# DIV30.net
KiCad netlist of a schematic drawn in Altium Designer
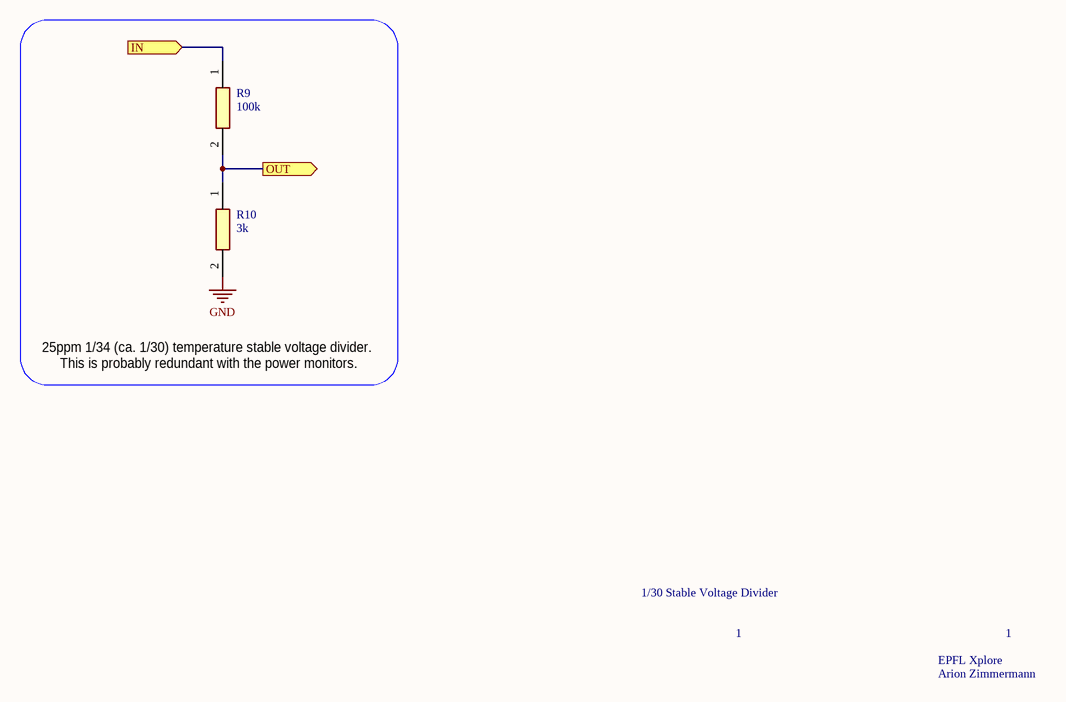
[diagram p0: DIV30.SchDoc]

(export (version "E")
  (design (tool "Eeschema 10.0.6"))
  (components
    (comp (ref "R9")
      (value "100k")
      (footprint "SamacSys:RESC1608X55N")
      (description "Resistor")
      (fields (field (name "MANUFACTURER_PART_NUMBER") "TNPW0603100KBEEA"))
      (libsource (lib "SamacSys") (part "TNPW0603100KBEEA"))
    )
    (comp (ref "R10")
      (value "3k")
      (footprint "SamacSys:RESC1608X55N")
      (description "Resistor")
      (fields
        (field (name "MANUFACTURER_PART_NUMBER") "TNPW06033K00BEEA")
        (field (name "MOUSER PART NUMBER") "71-TNPW06033K00BEEA")
      )
      (libsource (lib "SamacSys") (part "TNPW06033K00BEEA"))
    )
  )
  (nets
    (net (code "1") (name "/IN") (class "Default")
      (node (ref "R9") (pin "1") (pinfunction "1_1") (pintype "passive"))
    )
    (net (code "2") (name "/OUT") (class "Default")
      (node (ref "R10") (pin "1") (pinfunction "1_1") (pintype "passive"))
      (node (ref "R9") (pin "2") (pinfunction "2_2") (pintype "passive"))
    )
    (net (code "3") (name "GND") (class "Default")
      (node (ref "R10") (pin "2") (pinfunction "2_2") (pintype "passive"))
    )
  )
)
